# valiant_v2.net
KiCad netlist of a schematic drawn in EAGLE
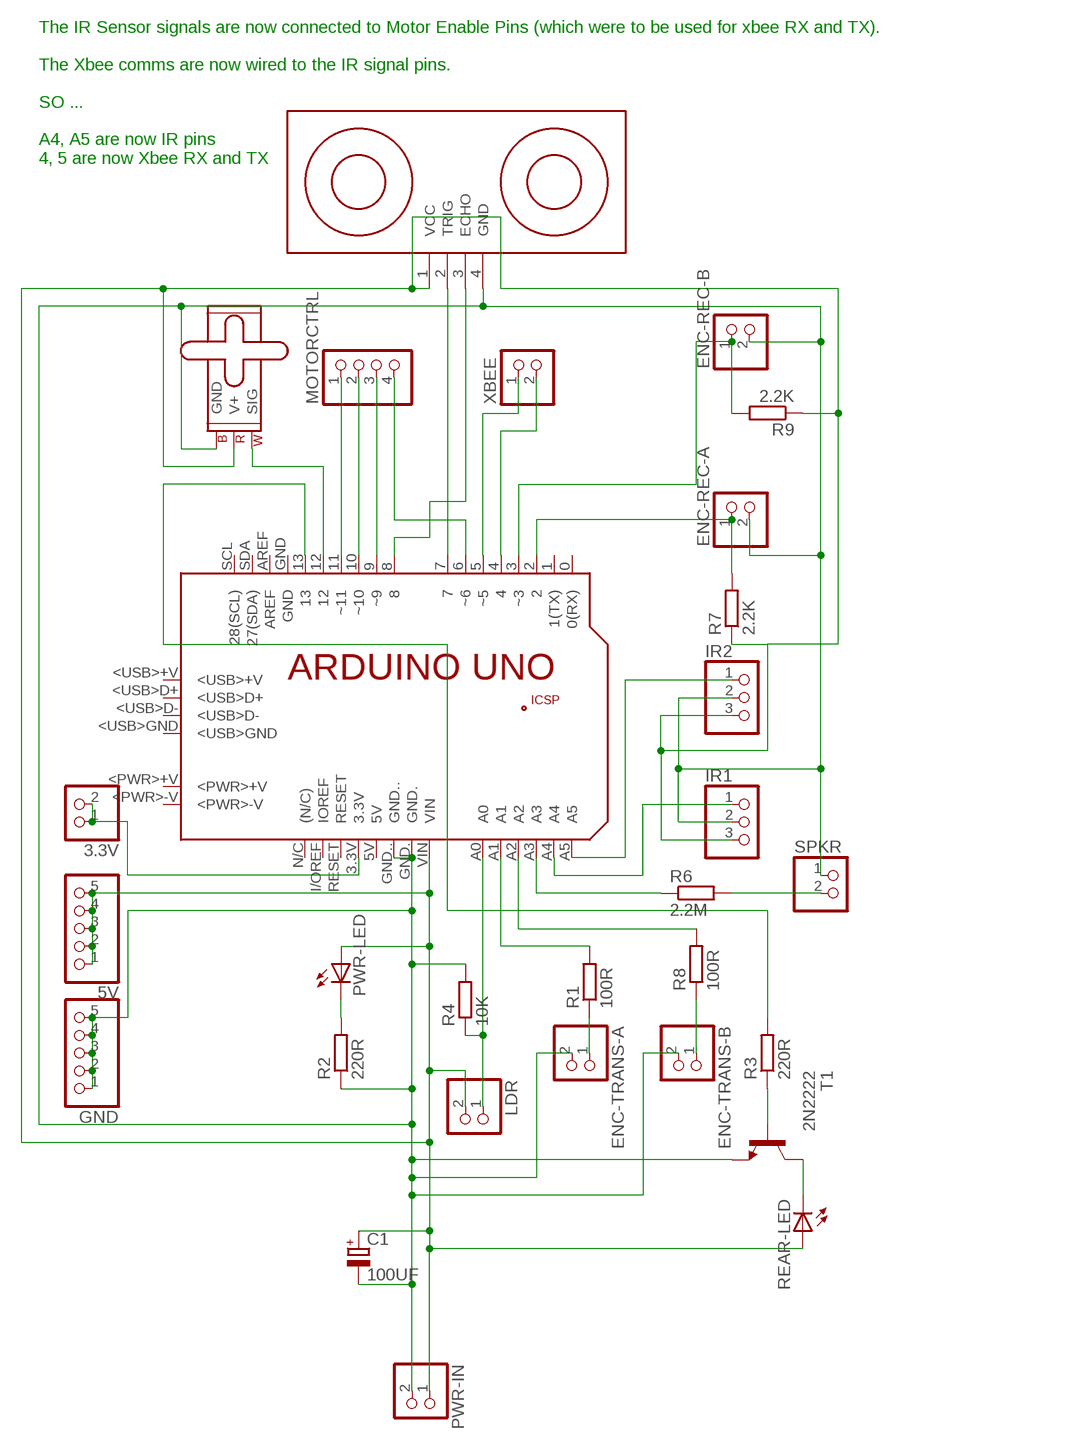
[diagram p0: schematic, sheet 1]

(export (version "E")
  (design (tool "Eeschema 10.0.6"))
  (components
    (comp (ref "3.3V")
      (value "PINHD-1X2")
      (footprint "eagle-import:1X02")
      (libsource (lib "eagle-import") (part "PINHD-1X2"))
    )
    (comp (ref "5V")
      (value "PINHD-1X5")
      (footprint "eagle-import:1X05")
      (libsource (lib "eagle-import") (part "PINHD-1X5"))
    )
    (comp (ref "C1")
      (value "100UF")
      (footprint "eagle-import:E2,5-6E")
      (libsource (lib "eagle-import") (part "CPOL-EUE2,5-6E"))
    )
    (comp (ref "ENC-REC-A")
      (value "PINHD-1X2")
      (footprint "eagle-import:1X02")
      (libsource (lib "eagle-import") (part "PINHD-1X2"))
    )
    (comp (ref "ENC-REC-B")
      (value "PINHD-1X2")
      (footprint "eagle-import:1X02")
      (libsource (lib "eagle-import") (part "PINHD-1X2"))
    )
    (comp (ref "ENC-TRANS-A")
      (value "PINHD-1X2")
      (footprint "eagle-import:1X02")
      (libsource (lib "eagle-import") (part "PINHD-1X2"))
    )
    (comp (ref "ENC-TRANS-B")
      (value "PINHD-1X2")
      (footprint "eagle-import:1X02")
      (libsource (lib "eagle-import") (part "PINHD-1X2"))
    )
    (comp (ref "GND")
      (value "PINHD-1X5")
      (footprint "eagle-import:1X05")
      (libsource (lib "eagle-import") (part "PINHD-1X5"))
    )
    (comp (ref "IR1")
      (value "PINHD-1X3")
      (footprint "eagle-import:1X03")
      (libsource (lib "eagle-import") (part "PINHD-1X3"))
    )
    (comp (ref "IR2")
      (value "PINHD-1X3")
      (footprint "eagle-import:1X03")
      (libsource (lib "eagle-import") (part "PINHD-1X3"))
    )
    (comp (ref "LDR")
      (value "PINHD-1X2")
      (footprint "eagle-import:1X02")
      (libsource (lib "eagle-import") (part "PINHD-1X2"))
    )
    (comp (ref "M1")
      (value "SMALL_SERVO")
      (footprint "eagle-import:1X03")
      (libsource (lib "eagle-import") (part "SMALL_SERVO"))
    )
    (comp (ref "MOTORCTRL")
      (value "PINHD-1X4")
      (footprint "eagle-import:1X04")
      (libsource (lib "eagle-import") (part "PINHD-1X4"))
    )
    (comp (ref "PCB1")
      (value "ARDUINO_UNO")
      (footprint "eagle-import:ARDUINO_UNO")
      (libsource (lib "eagle-import") (part "ARDUINO_UNO"))
    )
    (comp (ref "PWR-IN")
      (value "PINHD-1X2")
      (footprint "eagle-import:1X02")
      (libsource (lib "eagle-import") (part "PINHD-1X2"))
    )
    (comp (ref "PWR-LED")
      (value "LED5MM")
      (footprint "eagle-import:LED5MM")
      (libsource (lib "eagle-import") (part "LED5MM"))
    )
    (comp (ref "R1")
      (value "100R")
      (footprint "eagle-import:0204_7")
      (libsource (lib "eagle-import") (part "R-EU_0204/7"))
    )
    (comp (ref "R2")
      (value "220R")
      (footprint "eagle-import:0204_7")
      (libsource (lib "eagle-import") (part "R-EU_0204/7"))
    )
    (comp (ref "R3")
      (value "220R")
      (footprint "eagle-import:0204_7")
      (libsource (lib "eagle-import") (part "R-EU_0204/7"))
    )
    (comp (ref "R4")
      (value "10K")
      (footprint "eagle-import:0204_7")
      (libsource (lib "eagle-import") (part "R-EU_0204/7"))
    )
    (comp (ref "R6")
      (value "2.2M")
      (footprint "eagle-import:0204_7")
      (libsource (lib "eagle-import") (part "R-EU_0204/7"))
    )
    (comp (ref "R7")
      (value "2.2K")
      (footprint "eagle-import:0204_7")
      (libsource (lib "eagle-import") (part "R-EU_0204/7"))
    )
    (comp (ref "R8")
      (value "100R")
      (footprint "eagle-import:0204_7")
      (libsource (lib "eagle-import") (part "R-EU_0204/7"))
    )
    (comp (ref "R9")
      (value "2.2K")
      (footprint "eagle-import:0204_7")
      (libsource (lib "eagle-import") (part "R-EU_0204/7"))
    )
    (comp (ref "REAR-LED")
      (value "LED5MM")
      (footprint "eagle-import:LED5MM")
      (libsource (lib "eagle-import") (part "LED5MM"))
    )
    (comp (ref "SPKR")
      (value "PINHD-1X2")
      (footprint "eagle-import:1X02")
      (libsource (lib "eagle-import") (part "PINHD-1X2"))
    )
    (comp (ref "T1")
      (value "2N2222")
      (footprint "eagle-import:TO92-EBC-OVAL")
      (libsource (lib "eagle-import") (part "2N2222"))
    )
    (comp (ref "U$1")
      (value "ULTRASONIC-HC-SR04#V")
      (footprint "eagle-import:ULTRASONIC-HC-SR04#V")
      (libsource (lib "eagle-import") (part "ULTRASONIC-HC-SR04#V"))
    )
    (comp (ref "XBEE")
      (value "PINHD-1X2")
      (footprint "eagle-import:1X02")
      (libsource (lib "eagle-import") (part "PINHD-1X2"))
    )
  )
  (nets
    (net (code "1") (name "Net-(3.3V-Pad1)") (class "Default")
      (node (ref "3.3V") (pin "1") (pinfunction "1_1") (pintype "passive"))
      (node (ref "3.3V") (pin "2") (pinfunction "2_2") (pintype "passive"))
      (node (ref "PCB1") (pin "3.3V") (pinfunction "3.3V_3.3V") (pintype "bidirectional"))
    )
    (net (code "2") (name "Net-(ENC-REC-A-Pad1)") (class "Default")
      (node (ref "ENC-REC-A") (pin "1") (pinfunction "1_1") (pintype "passive"))
      (node (ref "PCB1") (pin "2") (pinfunction "2_2") (pintype "bidirectional"))
      (node (ref "R7") (pin "2") (pinfunction "2_2") (pintype "passive"))
    )
    (net (code "3") (name "Net-(ENC-TRANS-A-Pad1)") (class "Default")
      (node (ref "ENC-TRANS-A") (pin "1") (pinfunction "1_1") (pintype "passive"))
      (node (ref "R1") (pin "1") (pinfunction "1_1") (pintype "passive"))
    )
    (net (code "4") (name "Net-(ENC-TRANS-B-Pad1)") (class "Default")
      (node (ref "ENC-TRANS-B") (pin "1") (pinfunction "1_1") (pintype "passive"))
      (node (ref "R8") (pin "1") (pinfunction "1_1") (pintype "passive"))
    )
    (net (code "5") (name "Net-(IR1-Pad1)") (class "Default")
      (node (ref "IR1") (pin "1") (pinfunction "1_1") (pintype "passive"))
      (node (ref "PCB1") (pin "A4") (pinfunction "A4_A4") (pintype "bidirectional"))
    )
    (net (code "6") (name "Net-(IR2-Pad1)") (class "Default")
      (node (ref "IR2") (pin "1") (pinfunction "1_1") (pintype "passive"))
      (node (ref "PCB1") (pin "A5") (pinfunction "A5_A5") (pintype "bidirectional"))
    )
    (net (code "7") (name "Net-(LDR-Pad1)") (class "Default")
      (node (ref "LDR") (pin "1") (pinfunction "1_1") (pintype "passive"))
      (node (ref "PCB1") (pin "A0") (pinfunction "A0_A0") (pintype "bidirectional"))
      (node (ref "R4") (pin "1") (pinfunction "1_1") (pintype "passive"))
    )
    (net (code "8") (name "Net-(M1-GND)") (class "Default")
      (node (ref "C1") (pin "-") (pinfunction "-_-") (pintype "passive"))
      (node (ref "ENC-REC-A") (pin "2") (pinfunction "2_2") (pintype "passive"))
      (node (ref "ENC-REC-B") (pin "2") (pinfunction "2_2") (pintype "passive"))
      (node (ref "ENC-TRANS-A") (pin "2") (pinfunction "2_2") (pintype "passive"))
      (node (ref "ENC-TRANS-B") (pin "2") (pinfunction "2_2") (pintype "passive"))
      (node (ref "GND") (pin "1") (pinfunction "1_1") (pintype "passive"))
      (node (ref "GND") (pin "2") (pinfunction "2_2") (pintype "passive"))
      (node (ref "GND") (pin "3") (pinfunction "3_3") (pintype "passive"))
      (node (ref "GND") (pin "4") (pinfunction "4_4") (pintype "passive"))
      (node (ref "GND") (pin "5") (pinfunction "5_5") (pintype "passive"))
      (node (ref "IR1") (pin "2") (pinfunction "2_2") (pintype "passive"))
      (node (ref "IR2") (pin "2") (pinfunction "2_2") (pintype "passive"))
      (node (ref "M1") (pin "3") (pinfunction "GND_3") (pintype "bidirectional"))
      (node (ref "PCB1") (pin "GND.") (pinfunction "GND._GND.") (pintype "bidirectional"))
      (node (ref "PCB1") (pin "GND..") (pinfunction "GND.._GND..") (pintype "bidirectional"))
      (node (ref "PWR-IN") (pin "2") (pinfunction "2_2") (pintype "passive"))
      (node (ref "R2") (pin "1") (pinfunction "1_1") (pintype "passive"))
      (node (ref "R4") (pin "2") (pinfunction "2_2") (pintype "passive"))
      (node (ref "SPKR") (pin "1") (pinfunction "1_1") (pintype "passive"))
      (node (ref "T1") (pin "E") (pinfunction "E_E") (pintype "passive"))
      (node (ref "U$1") (pin "4") (pinfunction "GND_4") (pintype "power_in"))
    )
    (net (code "9") (name "Net-(M1-SIG)") (class "Default")
      (node (ref "M1") (pin "1") (pinfunction "SIG_1") (pintype "bidirectional"))
      (node (ref "PCB1") (pin "12") (pinfunction "12_12") (pintype "bidirectional"))
    )
    (net (code "10") (name "Net-(M1-V+)") (class "Default")
      (node (ref "5V") (pin "1") (pinfunction "1_1") (pintype "passive"))
      (node (ref "5V") (pin "2") (pinfunction "2_2") (pintype "passive"))
      (node (ref "5V") (pin "3") (pinfunction "3_3") (pintype "passive"))
      (node (ref "5V") (pin "4") (pinfunction "4_4") (pintype "passive"))
      (node (ref "5V") (pin "5") (pinfunction "5_5") (pintype "passive"))
      (node (ref "C1") (pin "+") (pinfunction "+_+") (pintype "passive"))
      (node (ref "IR1") (pin "3") (pinfunction "3_3") (pintype "passive"))
      (node (ref "IR2") (pin "3") (pinfunction "3_3") (pintype "passive"))
      (node (ref "LDR") (pin "2") (pinfunction "2_2") (pintype "passive"))
      (node (ref "M1") (pin "2") (pinfunction "V+_2") (pintype "bidirectional"))
      (node (ref "PCB1") (pin "VIN") (pinfunction "VIN_VIN") (pintype "bidirectional"))
      (node (ref "PWR-IN") (pin "1") (pinfunction "1_1") (pintype "passive"))
      (node (ref "PWR-LED") (pin "A") (pinfunction "A_A") (pintype "passive"))
      (node (ref "R7") (pin "1") (pinfunction "1_1") (pintype "passive"))
      (node (ref "R9") (pin "1") (pinfunction "1_1") (pintype "passive"))
      (node (ref "REAR-LED") (pin "A") (pinfunction "A_A") (pintype "passive"))
      (node (ref "U$1") (pin "1") (pinfunction "VCC_1") (pintype "power_in"))
    )
    (net (code "11") (name "Net-(PCB1-Pad4)") (class "Default")
      (node (ref "PCB1") (pin "4") (pinfunction "4_4") (pintype "bidirectional"))
      (node (ref "XBEE") (pin "2") (pinfunction "2_2") (pintype "passive"))
    )
    (net (code "12") (name "Net-(PCB1-Pad13)") (class "Default")
      (node (ref "PCB1") (pin "13") (pinfunction "13_13") (pintype "bidirectional"))
      (node (ref "R3") (pin "2") (pinfunction "2_2") (pintype "passive"))
    )
    (net (code "13") (name "Net-(PCB1-PadA1)") (class "Default")
      (node (ref "PCB1") (pin "A1") (pinfunction "A1_A1") (pintype "bidirectional"))
      (node (ref "R1") (pin "2") (pinfunction "2_2") (pintype "passive"))
    )
    (net (code "14") (name "Net-(PCB1-PadA2)") (class "Default")
      (node (ref "PCB1") (pin "A2") (pinfunction "A2_A2") (pintype "bidirectional"))
      (node (ref "R8") (pin "2") (pinfunction "2_2") (pintype "passive"))
    )
    (net (code "15") (name "Net-(PCB1-PadA3)") (class "Default")
      (node (ref "PCB1") (pin "A3") (pinfunction "A3_A3") (pintype "bidirectional"))
      (node (ref "R6") (pin "1") (pinfunction "1_1") (pintype "passive"))
    )
    (net (code "16") (name "Net-(PCB1-~{3})") (class "Default")
      (node (ref "ENC-REC-B") (pin "1") (pinfunction "1_1") (pintype "passive"))
      (node (ref "PCB1") (pin "3") (pinfunction "~{3}_3") (pintype "bidirectional"))
      (node (ref "R9") (pin "2") (pinfunction "2_2") (pintype "passive"))
    )
    (net (code "17") (name "Net-(PCB1-~{5})") (class "Default")
      (node (ref "PCB1") (pin "5") (pinfunction "~{5}_5") (pintype "bidirectional"))
      (node (ref "XBEE") (pin "1") (pinfunction "1_1") (pintype "passive"))
    )
    (net (code "18") (name "Net-(PCB1-~{6})") (class "Default")
      (node (ref "MOTORCTRL") (pin "4") (pinfunction "4_4") (pintype "passive"))
      (node (ref "PCB1") (pin "6") (pinfunction "~{6}_6") (pintype "bidirectional"))
    )
    (net (code "19") (name "Net-(PCB1-~{9})") (class "Default")
      (node (ref "MOTORCTRL") (pin "3") (pinfunction "3_3") (pintype "passive"))
      (node (ref "PCB1") (pin "9") (pinfunction "~{9}_9") (pintype "bidirectional"))
    )
    (net (code "20") (name "Net-(PCB1-~{10})") (class "Default")
      (node (ref "MOTORCTRL") (pin "2") (pinfunction "2_2") (pintype "passive"))
      (node (ref "PCB1") (pin "10") (pinfunction "~{10}_10") (pintype "bidirectional"))
    )
    (net (code "21") (name "Net-(PCB1-~{11})") (class "Default")
      (node (ref "MOTORCTRL") (pin "1") (pinfunction "1_1") (pintype "passive"))
      (node (ref "PCB1") (pin "11") (pinfunction "~{11}_11") (pintype "bidirectional"))
    )
    (net (code "22") (name "Net-(PWR-LED-C)") (class "Default")
      (node (ref "PWR-LED") (pin "K") (pinfunction "C_K") (pintype "passive"))
      (node (ref "R2") (pin "2") (pinfunction "2_2") (pintype "passive"))
    )
    (net (code "23") (name "Net-(R3-Pad1)") (class "Default")
      (node (ref "R3") (pin "1") (pinfunction "1_1") (pintype "passive"))
      (node (ref "T1") (pin "B") (pinfunction "B_B") (pintype "passive"))
    )
    (net (code "24") (name "Net-(R6-Pad2)") (class "Default")
      (node (ref "R6") (pin "2") (pinfunction "2_2") (pintype "passive"))
      (node (ref "SPKR") (pin "2") (pinfunction "2_2") (pintype "passive"))
    )
    (net (code "25") (name "Net-(REAR-LED-C)") (class "Default")
      (node (ref "REAR-LED") (pin "K") (pinfunction "C_K") (pintype "passive"))
      (node (ref "T1") (pin "C") (pinfunction "C_C") (pintype "passive"))
    )
    (net (code "26") (name "Net-(U$1-ECHO)") (class "Default")
      (node (ref "PCB1") (pin "8") (pinfunction "8_8") (pintype "bidirectional"))
      (node (ref "U$1") (pin "3") (pinfunction "ECHO_3") (pintype "output"))
    )
    (net (code "27") (name "Net-(U$1-TRIG)") (class "Default")
      (node (ref "PCB1") (pin "7") (pinfunction "7_7") (pintype "bidirectional"))
      (node (ref "U$1") (pin "2") (pinfunction "TRIG_2") (pintype "input"))
    )
    (net (code "28") (name "unconnected-(PCB1-(N{slash}C)-PadN{slash}C)") (class "Default")
      (node (ref "PCB1") (pin "N/C") (pinfunction "(N/C)_N/C") (pintype "bidirectional"))
    )
    (net (code "29") (name "unconnected-(PCB1-0(RX)-Pad0)") (class "Default")
      (node (ref "PCB1") (pin "0") (pinfunction "0(RX)_0") (pintype "bidirectional"))
    )
    (net (code "30") (name "unconnected-(PCB1-1(TX)-Pad1)") (class "Default")
      (node (ref "PCB1") (pin "1") (pinfunction "1(TX)_1") (pintype "bidirectional"))
    )
    (net (code "31") (name "unconnected-(PCB1-27(SDA)-PadSDA)") (class "Default")
      (node (ref "PCB1") (pin "SDA") (pinfunction "27(SDA)_SDA") (pintype "bidirectional"))
    )
    (net (code "32") (name "unconnected-(PCB1-28(SCL)-PadSCL)") (class "Default")
      (node (ref "PCB1") (pin "SCL") (pinfunction "28(SCL)_SCL") (pintype "bidirectional"))
    )
    (net (code "33") (name "unconnected-(PCB1-IOREF-PadI{slash}OREF)") (class "Default")
      (node (ref "PCB1") (pin "I/OREF") (pinfunction "IOREF_I/OREF") (pintype "bidirectional"))
    )
    (net (code "34") (name "unconnected-(PCB1-Pad+5V)") (class "Default")
      (node (ref "PCB1") (pin "+5V") (pinfunction "+5V_+5V") (pintype "bidirectional"))
    )
    (net (code "35") (name "unconnected-(PCB1-Pad5V)") (class "Default")
      (node (ref "PCB1") (pin "5V") (pinfunction "5V_5V") (pintype "bidirectional"))
    )
    (net (code "36") (name "unconnected-(PCB1-Pad<PWR>+V)") (class "Default")
      (node (ref "PCB1") (pin "<PWR>+V") (pinfunction "<PWR>+V_<PWR>+V") (pintype "bidirectional"))
    )
    (net (code "37") (name "unconnected-(PCB1-Pad<PWR>-V)") (class "Default")
      (node (ref "PCB1") (pin "<PWR>-V") (pinfunction "<PWR>-V_<PWR>-V") (pintype "bidirectional"))
    )
    (net (code "38") (name "unconnected-(PCB1-Pad<USB>+V)") (class "Default")
      (node (ref "PCB1") (pin "<USB>+V") (pinfunction "<USB>+V_<USB>+V") (pintype "bidirectional"))
    )
    (net (code "39") (name "unconnected-(PCB1-Pad<USB>D+)") (class "Default")
      (node (ref "PCB1") (pin "<USB>D+") (pinfunction "<USB>D+_<USB>D+") (pintype "bidirectional"))
    )
    (net (code "40") (name "unconnected-(PCB1-Pad<USB>D-)") (class "Default")
      (node (ref "PCB1") (pin "<USB>D-") (pinfunction "<USB>D-_<USB>D-") (pintype "bidirectional"))
    )
    (net (code "41") (name "unconnected-(PCB1-Pad<USB>GND)") (class "Default")
      (node (ref "PCB1") (pin "<USB>GND") (pinfunction "<USB>GND_<USB>GND") (pintype "bidirectional"))
    )
    (net (code "42") (name "unconnected-(PCB1-PadAREF)") (class "Default")
      (node (ref "PCB1") (pin "AREF") (pinfunction "AREF_AREF") (pintype "bidirectional"))
    )
    (net (code "43") (name "unconnected-(PCB1-PadGND)") (class "Default")
      (node (ref "PCB1") (pin "GND") (pinfunction "GND_GND") (pintype "bidirectional"))
    )
    (net (code "44") (name "unconnected-(PCB1-PadGND_)") (class "Default")
      (node (ref "PCB1") (pin "GND_") (pinfunction "GND__GND_") (pintype "bidirectional"))
    )
    (net (code "45") (name "unconnected-(PCB1-PadMISO)") (class "Default")
      (node (ref "PCB1") (pin "MISO") (pinfunction "MISO_MISO") (pintype "bidirectional"))
    )
    (net (code "46") (name "unconnected-(PCB1-PadMOSI)") (class "Default")
      (node (ref "PCB1") (pin "MOSI") (pinfunction "MOSI_MOSI") (pintype "bidirectional"))
    )
    (net (code "47") (name "unconnected-(PCB1-PadRESET)") (class "Default")
      (node (ref "PCB1") (pin "RESET") (pinfunction "RESET_RESET") (pintype "bidirectional"))
    )
    (net (code "48") (name "unconnected-(PCB1-PadRESET.)") (class "Default")
      (node (ref "PCB1") (pin "RESET.") (pinfunction "RESET._RESET.") (pintype "bidirectional"))
    )
    (net (code "49") (name "unconnected-(PCB1-PadSCK)") (class "Default")
      (node (ref "PCB1") (pin "SCK") (pinfunction "SCK_SCK") (pintype "bidirectional"))
    )
  )
)
